# Home_Automation_Nodes.net
KiCad netlist of a schematic drawn in EAGLE
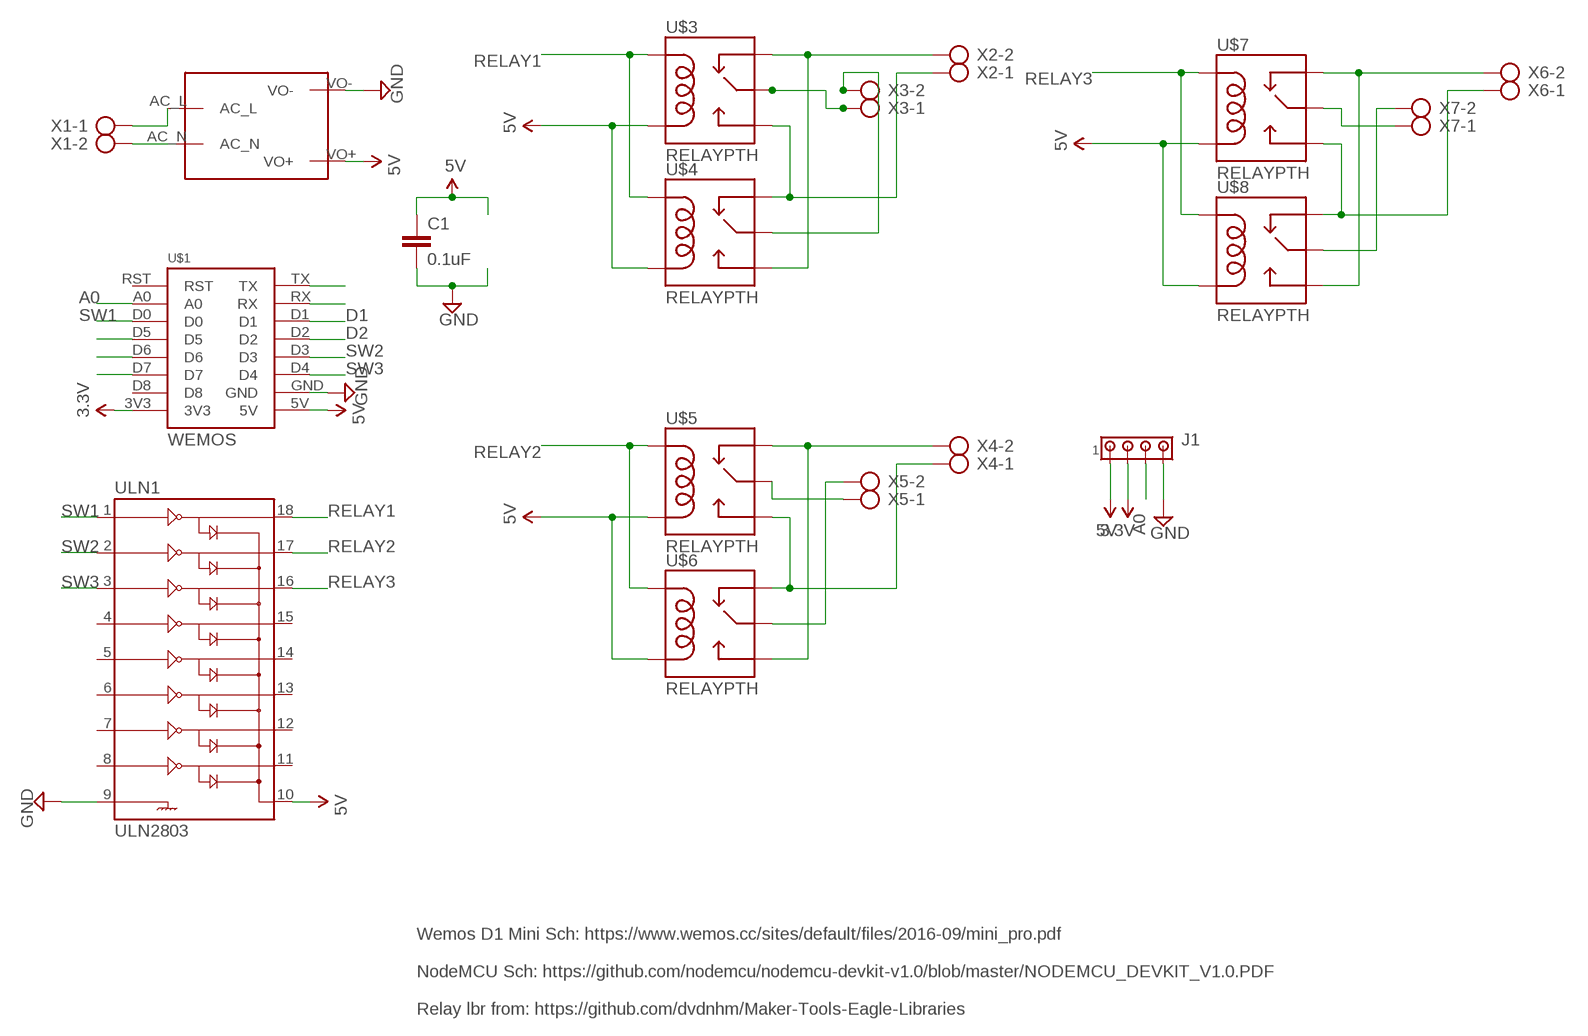
[diagram p0: schematic, sheet 1]

(export (version "E")
  (design (tool "Eeschema 10.0.6"))
  (components
    (comp (ref "C1")
      (value "0.1uF")
      (footprint "eagle-import:C025-025X050")
      (libsource (lib "eagle-import") (part "C-EU025-025X050"))
    )
    (comp (ref "J1")
      (value "MTA04-100")
      (footprint "eagle-import:10X04MTA")
      (libsource (lib "eagle-import") (part "MTA04-100"))
    )
    (comp (ref "U$1")
      (value "WEMOS")
      (footprint "eagle-import:WEMOS")
      (libsource (lib "eagle-import") (part "WEMOS"))
    )
    (comp (ref "U$2")
      (value "MAINS_CONVERTERS")
      (footprint "eagle-import:HLK-PM01")
      (libsource (lib "eagle-import") (part "MAINS_CONVERTERS"))
    )
    (comp (ref "U$3")
      (value "RELAYPTH")
      (footprint "eagle-import:SRD-05VDC-SL-C")
      (libsource (lib "eagle-import") (part "RELAYPTH"))
    )
    (comp (ref "U$4")
      (value "RELAYPTH")
      (footprint "eagle-import:SRD-05VDC-SL-C")
      (libsource (lib "eagle-import") (part "RELAYPTH"))
    )
    (comp (ref "U$5")
      (value "RELAYPTH")
      (footprint "eagle-import:SRD-05VDC-SL-C")
      (libsource (lib "eagle-import") (part "RELAYPTH"))
    )
    (comp (ref "U$6")
      (value "RELAYPTH")
      (footprint "eagle-import:SRD-05VDC-SL-C")
      (libsource (lib "eagle-import") (part "RELAYPTH"))
    )
    (comp (ref "U$7")
      (value "RELAYPTH")
      (footprint "eagle-import:SRD-05VDC-SL-C")
      (libsource (lib "eagle-import") (part "RELAYPTH"))
    )
    (comp (ref "U$8")
      (value "RELAYPTH")
      (footprint "eagle-import:SRD-05VDC-SL-C")
      (libsource (lib "eagle-import") (part "RELAYPTH"))
    )
    (comp (ref "ULN1")
      (value "ULN2803")
      (footprint "eagle-import:DIL18")
      (libsource (lib "eagle-import") (part "ULN2803DIP"))
    )
    (comp (ref "X1")
      (value "AK300/2")
      (footprint "eagle-import:AK300_2")
      (libsource (lib "eagle-import") (part "AK300/2"))
    )
    (comp (ref "X2")
      (value "AK300/2")
      (footprint "eagle-import:AK300_2")
      (libsource (lib "eagle-import") (part "AK300/2"))
    )
    (comp (ref "X3")
      (value "AK300/2")
      (footprint "eagle-import:AK300_2")
      (libsource (lib "eagle-import") (part "AK300/2"))
    )
    (comp (ref "X4")
      (value "AK300/2")
      (footprint "eagle-import:AK300_2")
      (libsource (lib "eagle-import") (part "AK300/2"))
    )
    (comp (ref "X5")
      (value "AK300/2")
      (footprint "eagle-import:AK300_2")
      (libsource (lib "eagle-import") (part "AK300/2"))
    )
    (comp (ref "X6")
      (value "AK300/2")
      (footprint "eagle-import:AK300_2")
      (libsource (lib "eagle-import") (part "AK300/2"))
    )
    (comp (ref "X7")
      (value "AK300/2")
      (footprint "eagle-import:AK300_2")
      (libsource (lib "eagle-import") (part "AK300/2"))
    )
  )
  (nets
    (net (code "1") (name "/A0") (class "Default")
      (node (ref "J1") (pin "3") (pinfunction "3_3") (pintype "passive"))
      (node (ref "U$1") (pin "A0") (pinfunction "A0_A0") (pintype "bidirectional"))
    )
    (net (code "2") (name "/D1") (class "Default")
      (node (ref "U$1") (pin "D1") (pinfunction "D1_D1") (pintype "bidirectional"))
    )
    (net (code "3") (name "/D2") (class "Default")
      (node (ref "U$1") (pin "D2") (pinfunction "D2_D2") (pintype "bidirectional"))
    )
    (net (code "4") (name "/RELAY1") (class "Default")
      (node (ref "U$3") (pin "COIL1") (pinfunction "COIL1_COIL1") (pintype "bidirectional"))
      (node (ref "U$4") (pin "COIL1") (pinfunction "COIL1_COIL1") (pintype "bidirectional"))
      (node (ref "ULN1") (pin "18") (pinfunction "18_18") (pintype "bidirectional"))
    )
    (net (code "5") (name "/RELAY2") (class "Default")
      (node (ref "U$5") (pin "COIL1") (pinfunction "COIL1_COIL1") (pintype "bidirectional"))
      (node (ref "U$6") (pin "COIL1") (pinfunction "COIL1_COIL1") (pintype "bidirectional"))
      (node (ref "ULN1") (pin "17") (pinfunction "17_17") (pintype "bidirectional"))
    )
    (net (code "6") (name "/RELAY3") (class "Default")
      (node (ref "U$7") (pin "COIL1") (pinfunction "COIL1_COIL1") (pintype "bidirectional"))
      (node (ref "U$8") (pin "COIL1") (pinfunction "COIL1_COIL1") (pintype "bidirectional"))
      (node (ref "ULN1") (pin "16") (pinfunction "16_16") (pintype "bidirectional"))
    )
    (net (code "7") (name "/SW1") (class "Default")
      (node (ref "U$1") (pin "D0") (pinfunction "D0_D0") (pintype "bidirectional"))
      (node (ref "ULN1") (pin "1") (pinfunction "1_1") (pintype "bidirectional"))
    )
    (net (code "8") (name "/SW2") (class "Default")
      (node (ref "U$1") (pin "D3") (pinfunction "D3_D3") (pintype "bidirectional"))
      (node (ref "ULN1") (pin "2") (pinfunction "2_2") (pintype "bidirectional"))
    )
    (net (code "9") (name "/SW3") (class "Default")
      (node (ref "U$1") (pin "D4") (pinfunction "D4_D4") (pintype "bidirectional"))
      (node (ref "ULN1") (pin "3") (pinfunction "3_3") (pintype "bidirectional"))
    )
    (net (code "10") (name "3.3V") (class "Default")
      (node (ref "J1") (pin "2") (pinfunction "2_2") (pintype "passive"))
      (node (ref "U$1") (pin "3V3") (pinfunction "3V3_3V3") (pintype "bidirectional"))
    )
    (net (code "11") (name "5V") (class "Default")
      (node (ref "C1") (pin "1") (pinfunction "1_1") (pintype "passive"))
      (node (ref "J1") (pin "1") (pinfunction "1_1") (pintype "passive"))
      (node (ref "U$1") (pin "5V") (pinfunction "5V_5V") (pintype "bidirectional"))
      (node (ref "U$2") (pin "VO+") (pinfunction "VO+_VO+") (pintype "output"))
      (node (ref "U$3") (pin "COIL0") (pinfunction "COIL0_COIL0") (pintype "bidirectional"))
      (node (ref "U$4") (pin "COIL0") (pinfunction "COIL0_COIL0") (pintype "bidirectional"))
      (node (ref "U$5") (pin "COIL0") (pinfunction "COIL0_COIL0") (pintype "bidirectional"))
      (node (ref "U$6") (pin "COIL0") (pinfunction "COIL0_COIL0") (pintype "bidirectional"))
      (node (ref "U$7") (pin "COIL0") (pinfunction "COIL0_COIL0") (pintype "bidirectional"))
      (node (ref "U$8") (pin "COIL0") (pinfunction "COIL0_COIL0") (pintype "bidirectional"))
      (node (ref "ULN1") (pin "10") (pinfunction "10_10") (pintype "bidirectional"))
    )
    (net (code "12") (name "GND") (class "Default")
      (node (ref "C1") (pin "2") (pinfunction "2_2") (pintype "passive"))
      (node (ref "J1") (pin "4") (pinfunction "4_4") (pintype "passive"))
      (node (ref "U$1") (pin "GND") (pinfunction "GND_GND") (pintype "bidirectional"))
      (node (ref "U$2") (pin "VO-") (pinfunction "VO-_VO-") (pintype "output"))
      (node (ref "ULN1") (pin "9") (pinfunction "9_9") (pintype "bidirectional"))
    )
    (net (code "13") (name "Net-(U$3-SWCLOSE)") (class "Default")
      (node (ref "U$3") (pin "SWCLOSED") (pinfunction "SWCLOSE_SWCLOSED") (pintype "bidirectional"))
      (node (ref "U$4") (pin "SWOPEN") (pinfunction "SWOPEN_SWOPEN") (pintype "bidirectional"))
      (node (ref "X2") (pin "2") (pinfunction "KL_2") (pintype "passive"))
    )
    (net (code "14") (name "Net-(U$4-SWCLOSE)") (class "Default")
      (node (ref "U$3") (pin "SWOPEN") (pinfunction "SWOPEN_SWOPEN") (pintype "bidirectional"))
      (node (ref "U$4") (pin "SWCLOSED") (pinfunction "SWCLOSE_SWCLOSED") (pintype "bidirectional"))
      (node (ref "X2") (pin "1") (pinfunction "KL_1") (pintype "passive"))
    )
    (net (code "15") (name "Net-(U$5-SWCLOSE)") (class "Default")
      (node (ref "U$5") (pin "SWCLOSED") (pinfunction "SWCLOSE_SWCLOSED") (pintype "bidirectional"))
      (node (ref "U$6") (pin "SWOPEN") (pinfunction "SWOPEN_SWOPEN") (pintype "bidirectional"))
      (node (ref "X4") (pin "2") (pinfunction "KL_2") (pintype "passive"))
    )
    (net (code "16") (name "Net-(U$6-SWCLOSE)") (class "Default")
      (node (ref "U$5") (pin "SWOPEN") (pinfunction "SWOPEN_SWOPEN") (pintype "bidirectional"))
      (node (ref "U$6") (pin "SWCLOSED") (pinfunction "SWCLOSE_SWCLOSED") (pintype "bidirectional"))
      (node (ref "X4") (pin "1") (pinfunction "KL_1") (pintype "passive"))
    )
    (net (code "17") (name "Net-(U$7-SWCLOSE)") (class "Default")
      (node (ref "U$7") (pin "SWCLOSED") (pinfunction "SWCLOSE_SWCLOSED") (pintype "bidirectional"))
      (node (ref "U$8") (pin "SWOPEN") (pinfunction "SWOPEN_SWOPEN") (pintype "bidirectional"))
      (node (ref "X6") (pin "2") (pinfunction "KL_2") (pintype "passive"))
    )
    (net (code "18") (name "Net-(U$8-SWCLOSE)") (class "Default")
      (node (ref "U$7") (pin "SWOPEN") (pinfunction "SWOPEN_SWOPEN") (pintype "bidirectional"))
      (node (ref "U$8") (pin "SWCLOSED") (pinfunction "SWCLOSE_SWCLOSED") (pintype "bidirectional"))
      (node (ref "X6") (pin "1") (pinfunction "KL_1") (pintype "passive"))
    )
    (net (code "19") (name "Net-(X1A-KL)") (class "Default")
      (node (ref "U$2") (pin "AC_L") (pinfunction "AC_L_AC_L") (pintype "input"))
      (node (ref "X1") (pin "1") (pinfunction "KL_1") (pintype "passive"))
    )
    (net (code "20") (name "Net-(X1B-KL)") (class "Default")
      (node (ref "U$2") (pin "AC_N") (pinfunction "AC_N_AC_N") (pintype "input"))
      (node (ref "X1") (pin "2") (pinfunction "KL_2") (pintype "passive"))
    )
    (net (code "21") (name "Net-(X3A-KL)") (class "Default")
      (node (ref "U$3") (pin "SWCOMMON") (pinfunction "SWCOMMON_SWCOMMON") (pintype "bidirectional"))
      (node (ref "X3") (pin "1") (pinfunction "KL_1") (pintype "passive"))
    )
    (net (code "22") (name "Net-(X3B-KL)") (class "Default")
      (node (ref "U$4") (pin "SWCOMMON") (pinfunction "SWCOMMON_SWCOMMON") (pintype "bidirectional"))
      (node (ref "X3") (pin "2") (pinfunction "KL_2") (pintype "passive"))
    )
    (net (code "23") (name "Net-(X5A-KL)") (class "Default")
      (node (ref "U$5") (pin "SWCOMMON") (pinfunction "SWCOMMON_SWCOMMON") (pintype "bidirectional"))
      (node (ref "X5") (pin "1") (pinfunction "KL_1") (pintype "passive"))
    )
    (net (code "24") (name "Net-(X5B-KL)") (class "Default")
      (node (ref "U$6") (pin "SWCOMMON") (pinfunction "SWCOMMON_SWCOMMON") (pintype "bidirectional"))
      (node (ref "X5") (pin "2") (pinfunction "KL_2") (pintype "passive"))
    )
    (net (code "25") (name "Net-(X7A-KL)") (class "Default")
      (node (ref "U$7") (pin "SWCOMMON") (pinfunction "SWCOMMON_SWCOMMON") (pintype "bidirectional"))
      (node (ref "X7") (pin "1") (pinfunction "KL_1") (pintype "passive"))
    )
    (net (code "26") (name "Net-(X7B-KL)") (class "Default")
      (node (ref "U$8") (pin "SWCOMMON") (pinfunction "SWCOMMON_SWCOMMON") (pintype "bidirectional"))
      (node (ref "X7") (pin "2") (pinfunction "KL_2") (pintype "passive"))
    )
    (net (code "27") (name "unconnected-(U$1-PadD5)") (class "Default")
      (node (ref "U$1") (pin "D5") (pinfunction "D5_D5") (pintype "bidirectional"))
    )
    (net (code "28") (name "unconnected-(U$1-PadD6)") (class "Default")
      (node (ref "U$1") (pin "D6") (pinfunction "D6_D6") (pintype "bidirectional"))
    )
    (net (code "29") (name "unconnected-(U$1-PadD7)") (class "Default")
      (node (ref "U$1") (pin "D7") (pinfunction "D7_D7") (pintype "bidirectional"))
    )
    (net (code "30") (name "unconnected-(U$1-PadD8)") (class "Default")
      (node (ref "U$1") (pin "D8") (pinfunction "D8_D8") (pintype "bidirectional"))
    )
    (net (code "31") (name "unconnected-(U$1-PadRST)") (class "Default")
      (node (ref "U$1") (pin "RST") (pinfunction "RST_RST") (pintype "bidirectional"))
    )
    (net (code "32") (name "unconnected-(U$1-PadRX)") (class "Default")
      (node (ref "U$1") (pin "RX") (pinfunction "RX_RX") (pintype "bidirectional"))
    )
    (net (code "33") (name "unconnected-(U$1-PadTX)") (class "Default")
      (node (ref "U$1") (pin "TX") (pinfunction "TX_TX") (pintype "bidirectional"))
    )
    (net (code "34") (name "unconnected-(ULN1-Pad4)") (class "Default")
      (node (ref "ULN1") (pin "4") (pinfunction "4_4") (pintype "bidirectional"))
    )
    (net (code "35") (name "unconnected-(ULN1-Pad5)") (class "Default")
      (node (ref "ULN1") (pin "5") (pinfunction "5_5") (pintype "bidirectional"))
    )
    (net (code "36") (name "unconnected-(ULN1-Pad6)") (class "Default")
      (node (ref "ULN1") (pin "6") (pinfunction "6_6") (pintype "bidirectional"))
    )
    (net (code "37") (name "unconnected-(ULN1-Pad7)") (class "Default")
      (node (ref "ULN1") (pin "7") (pinfunction "7_7") (pintype "bidirectional"))
    )
    (net (code "38") (name "unconnected-(ULN1-Pad8)") (class "Default")
      (node (ref "ULN1") (pin "8") (pinfunction "8_8") (pintype "bidirectional"))
    )
    (net (code "39") (name "unconnected-(ULN1-Pad11)") (class "Default")
      (node (ref "ULN1") (pin "11") (pinfunction "11_11") (pintype "bidirectional"))
    )
    (net (code "40") (name "unconnected-(ULN1-Pad12)") (class "Default")
      (node (ref "ULN1") (pin "12") (pinfunction "12_12") (pintype "bidirectional"))
    )
    (net (code "41") (name "unconnected-(ULN1-Pad13)") (class "Default")
      (node (ref "ULN1") (pin "13") (pinfunction "13_13") (pintype "bidirectional"))
    )
    (net (code "42") (name "unconnected-(ULN1-Pad14)") (class "Default")
      (node (ref "ULN1") (pin "14") (pinfunction "14_14") (pintype "bidirectional"))
    )
    (net (code "43") (name "unconnected-(ULN1-Pad15)") (class "Default")
      (node (ref "ULN1") (pin "15") (pinfunction "15_15") (pintype "bidirectional"))
    )
  )
)
